# HEATING.net
KiCad netlist of a schematic drawn in Altium Designer
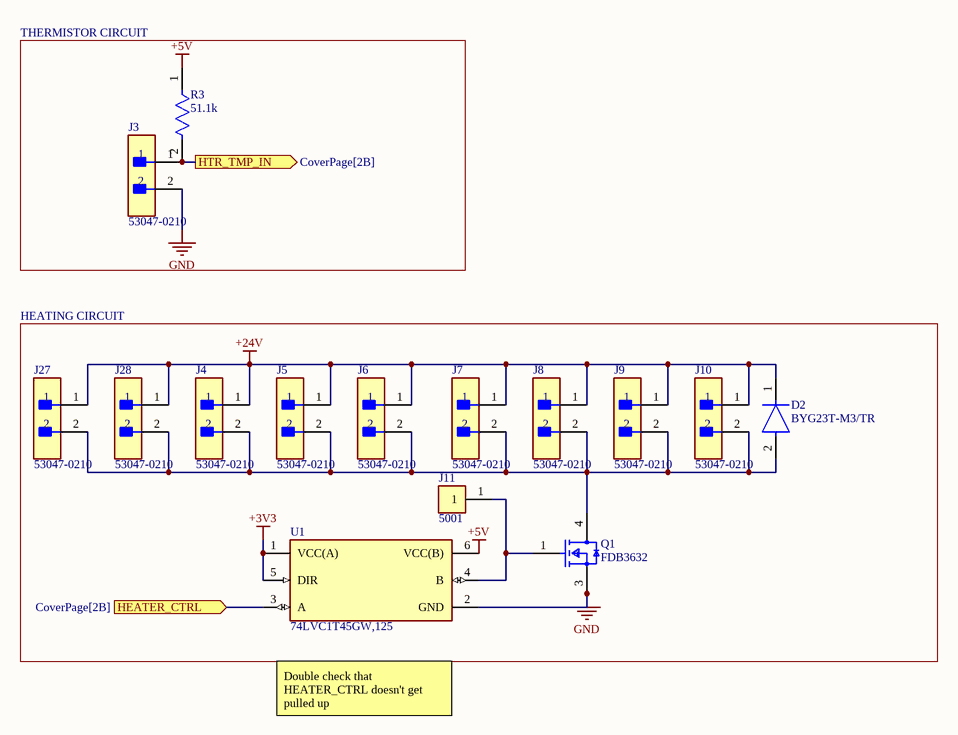
[diagram p0: HEATING.SchDoc]

(export (version "E")
  (design (tool "Eeschema 10.0.6"))
  (components
    (comp (ref "D2")
      (value "BYG23T-M3/TR")
      (footprint "FP-SMA-MFG")
      (description "DIODE AVALANCHE 1300V 1A DO214AC")
      (libsource (lib "Altium Content Vault") (part "d7152d700b627762746794eb795d46e"))
    )
    (comp (ref "J3")
      (value "53047-0210")
      (footprint "FP-53047-0210-MFG")
      (description "CONN HEADER VERT 2POS 1.25MM")
      (fields
        (field (name "OCTOPART") "https://octopart.com/53047-0210-molex-276772")
        (field (name "MANUFACTURER") "Molex")
      )
      (libsource (lib "Altium Content Vault") (part "3bc925449376181038e59eaffc5286c"))
    )
    (comp (ref "J4")
      (value "53047-0210")
      (footprint "FP-53047-0210-MFG")
      (description "CONN HEADER VERT 2POS 1.25MM")
      (fields
        (field (name "OCTOPART") "https://octopart.com/53047-0210-molex-276772")
        (field (name "MANUFACTURER") "Molex")
      )
      (libsource (lib "Altium Content Vault") (part "3bc925449376181038e59eaffc5286c"))
    )
    (comp (ref "J5")
      (value "53047-0210")
      (footprint "FP-53047-0210-MFG")
      (description "CONN HEADER VERT 2POS 1.25MM")
      (fields
        (field (name "OCTOPART") "https://octopart.com/53047-0210-molex-276772")
        (field (name "MANUFACTURER") "Molex")
      )
      (libsource (lib "Altium Content Vault") (part "3bc925449376181038e59eaffc5286c"))
    )
    (comp (ref "J6")
      (value "53047-0210")
      (footprint "FP-53047-0210-MFG")
      (description "CONN HEADER VERT 2POS 1.25MM")
      (fields
        (field (name "OCTOPART") "https://octopart.com/53047-0210-molex-276772")
        (field (name "MANUFACTURER") "Molex")
      )
      (libsource (lib "Altium Content Vault") (part "3bc925449376181038e59eaffc5286c"))
    )
    (comp (ref "J7")
      (value "53047-0210")
      (footprint "FP-53047-0210-MFG")
      (description "CONN HEADER VERT 2POS 1.25MM")
      (fields
        (field (name "OCTOPART") "https://octopart.com/53047-0210-molex-276772")
        (field (name "MANUFACTURER") "Molex")
      )
      (libsource (lib "Altium Content Vault") (part "3bc925449376181038e59eaffc5286c"))
    )
    (comp (ref "J8")
      (value "53047-0210")
      (footprint "FP-53047-0210-MFG")
      (description "CONN HEADER VERT 2POS 1.25MM")
      (fields
        (field (name "OCTOPART") "https://octopart.com/53047-0210-molex-276772")
        (field (name "MANUFACTURER") "Molex")
      )
      (libsource (lib "Altium Content Vault") (part "3bc925449376181038e59eaffc5286c"))
    )
    (comp (ref "J9")
      (value "53047-0210")
      (footprint "FP-53047-0210-MFG")
      (description "CONN HEADER VERT 2POS 1.25MM")
      (fields
        (field (name "OCTOPART") "https://octopart.com/53047-0210-molex-276772")
        (field (name "MANUFACTURER") "Molex")
      )
      (libsource (lib "Altium Content Vault") (part "3bc925449376181038e59eaffc5286c"))
    )
    (comp (ref "J10")
      (value "53047-0210")
      (footprint "FP-53047-0210-MFG")
      (description "CONN HEADER VERT 2POS 1.25MM")
      (fields
        (field (name "OCTOPART") "https://octopart.com/53047-0210-molex-276772")
        (field (name "MANUFACTURER") "Molex")
      )
      (libsource (lib "Altium Content Vault") (part "3bc925449376181038e59eaffc5286c"))
    )
    (comp (ref "J11")
      (value "5001")
      (footprint "FP-5001-MFG")
      (description "PC TEST POINT MINIATURE BLACK")
      (libsource (lib "Altium Content Vault") (part "1e4615820a309e3ce90f9e6d957b7fa"))
    )
    (comp (ref "J27")
      (value "53047-0210")
      (footprint "FP-53047-0210-MFG")
      (description "CONN HEADER VERT 2POS 1.25MM")
      (fields
        (field (name "OCTOPART") "https://octopart.com/53047-0210-molex-276772")
        (field (name "MANUFACTURER") "Molex")
      )
      (libsource (lib "Altium Content Vault") (part "3bc925449376181038e59eaffc5286c"))
    )
    (comp (ref "J28")
      (value "53047-0210")
      (footprint "FP-53047-0210-MFG")
      (description "CONN HEADER VERT 2POS 1.25MM")
      (fields
        (field (name "OCTOPART") "https://octopart.com/53047-0210-molex-276772")
        (field (name "MANUFACTURER") "Molex")
      )
      (libsource (lib "Altium Content Vault") (part "3bc925449376181038e59eaffc5286c"))
    )
    (comp (ref "Q1")
      (value "FDB3632")
      (footprint "FP-418AJ-MFG")
      (description "MOSFET N-CH 100V 80A D2PAK")
      (fields
        (field (name "MANUFACTURER") "ON Semiconductor")
        (field (name "OCTOPART") "https://octopart.com/fdb3632-on+semiconductor-84325670")
      )
      (libsource (lib "Altium Content Vault") (part "9dda50919618e2b74f88a68e272f5a4"))
    )
    (comp (ref "R3")
      (value "51.1k")
      (footprint "FP-RG2012-MFG")
      (description "Automotive Metal Thin Film Chip Resistor, 0805, 51.1kΩ, 0.1%, 25ppm/°C, 0.125W, 150V")
      (fields (field (name "TOLERANCE") "0.1%"))
      (libsource (lib "Altium Content Vault") (part "1029c3af85768c4190bb7ad29bc67b5"))
    )
    (comp (ref "U1")
      (value "74LVC1T45GW,125")
      (footprint "FP-SOT363-IPC_B")
      (description "IC TRNSLTR BIDIRECTIONAL 6TSSOP")
      (libsource (lib "Altium Content Vault") (part "bec2165475c94d7b6e4e459845695a2"))
    )
  )
  (nets
    (net (code "1") (name "+3V3") (class "Default")
      (node (ref "U1") (pin "1") (pinfunction "VCC(A)_1") (pintype "power_in"))
      (node (ref "U1") (pin "5") (pinfunction "DIR_5") (pintype "input"))
    )
    (net (code "2") (name "+5V") (class "Default")
      (node (ref "R3") (pin "1") (pinfunction "1_1") (pintype "passive"))
      (node (ref "U1") (pin "6") (pinfunction "VCC(B)_6") (pintype "power_in"))
    )
    (net (code "3") (name "+24V") (class "Default")
      (node (ref "D2") (pin "1") (pinfunction "C_1") (pintype "passive"))
      (node (ref "J10") (pin "1") (pinfunction "1_1") (pintype "passive"))
      (node (ref "J27") (pin "1") (pinfunction "1_1") (pintype "passive"))
      (node (ref "J28") (pin "1") (pinfunction "1_1") (pintype "passive"))
      (node (ref "J4") (pin "1") (pinfunction "1_1") (pintype "passive"))
      (node (ref "J5") (pin "1") (pinfunction "1_1") (pintype "passive"))
      (node (ref "J6") (pin "1") (pinfunction "1_1") (pintype "passive"))
      (node (ref "J7") (pin "1") (pinfunction "1_1") (pintype "passive"))
      (node (ref "J8") (pin "1") (pinfunction "1_1") (pintype "passive"))
      (node (ref "J9") (pin "1") (pinfunction "1_1") (pintype "passive"))
    )
    (net (code "4") (name "/HEATER_CTRL") (class "Default")
      (node (ref "U1") (pin "3") (pinfunction "A_3") (pintype "bidirectional"))
    )
    (net (code "5") (name "/HTR_TMP_IN") (class "Default")
      (node (ref "J3") (pin "1") (pinfunction "1_1") (pintype "passive"))
      (node (ref "R3") (pin "2") (pinfunction "2_2") (pintype "passive"))
    )
    (net (code "6") (name "GND") (class "Default")
      (node (ref "J3") (pin "2") (pinfunction "2_2") (pintype "passive"))
      (node (ref "Q1") (pin "3") (pinfunction "S_3") (pintype "passive"))
      (node (ref "U1") (pin "2") (pinfunction "GND_2") (pintype "power_in"))
    )
    (net (code "7") (name "Net-(D2-A)") (class "Default")
      (node (ref "D2") (pin "2") (pinfunction "A_2") (pintype "passive"))
      (node (ref "J10") (pin "2") (pinfunction "2_2") (pintype "passive"))
      (node (ref "J27") (pin "2") (pinfunction "2_2") (pintype "passive"))
      (node (ref "J28") (pin "2") (pinfunction "2_2") (pintype "passive"))
      (node (ref "J4") (pin "2") (pinfunction "2_2") (pintype "passive"))
      (node (ref "J5") (pin "2") (pinfunction "2_2") (pintype "passive"))
      (node (ref "J6") (pin "2") (pinfunction "2_2") (pintype "passive"))
      (node (ref "J7") (pin "2") (pinfunction "2_2") (pintype "passive"))
      (node (ref "J8") (pin "2") (pinfunction "2_2") (pintype "passive"))
      (node (ref "J9") (pin "2") (pinfunction "2_2") (pintype "passive"))
      (node (ref "Q1") (pin "4") (pinfunction "D_4") (pintype "passive"))
    )
    (net (code "8") (name "Net-(Q1-G)") (class "Default")
      (node (ref "J11") (pin "1") (pinfunction "1_1") (pintype "passive"))
      (node (ref "Q1") (pin "1") (pinfunction "G_1") (pintype "passive"))
      (node (ref "U1") (pin "4") (pinfunction "B_4") (pintype "bidirectional"))
    )
  )
)
